# tweeq-extMod_DualSidePB.net
KiCad netlist of a schematic drawn in EAGLE
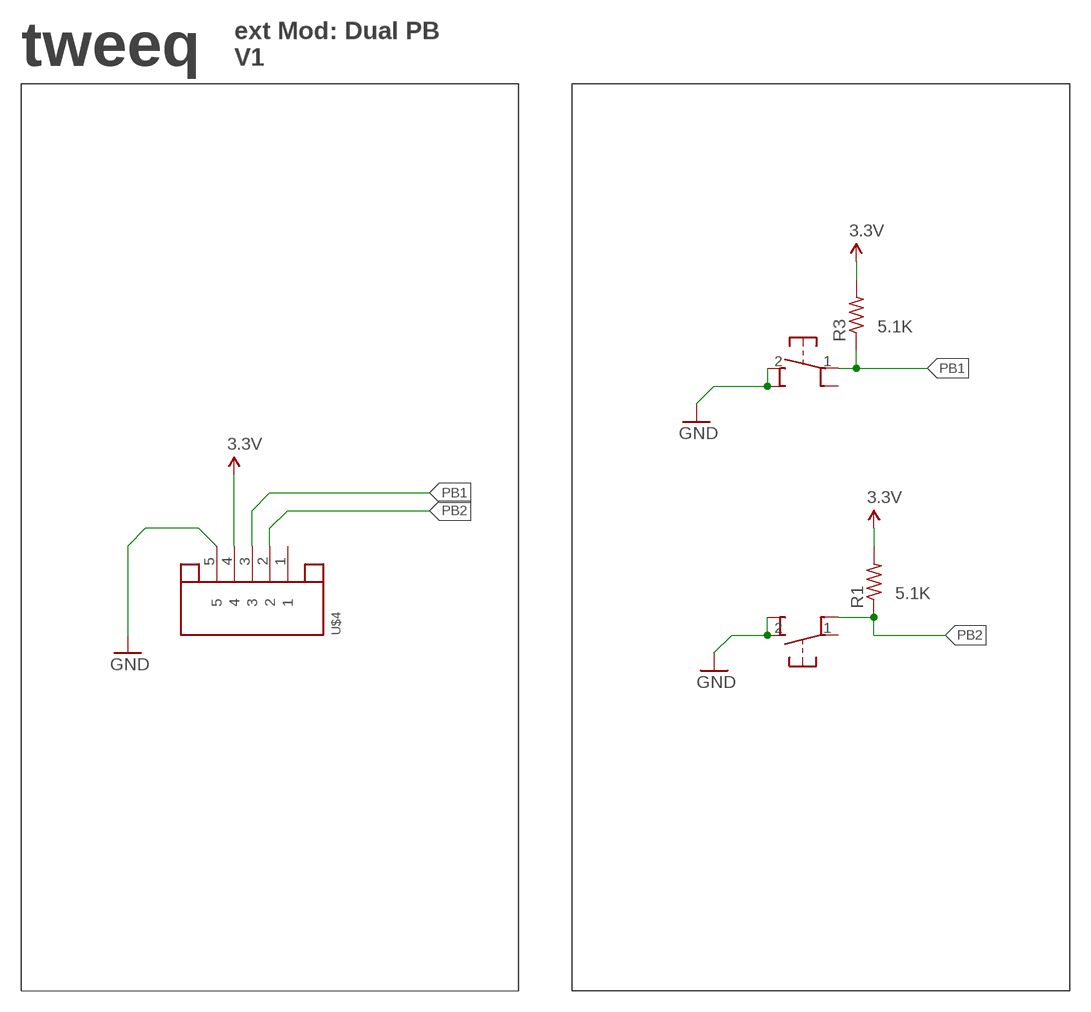
[diagram p0: schematic, sheet 1]

(export (version "E")
  (design (tool "Eeschema 10.0.6"))
  (components
    (comp (ref "R1")
      (value "5.1K")
      (footprint "eagle-import:R0402")
      (libsource (lib "eagle-import") (part "R-US_R0402"))
    )
    (comp (ref "R3")
      (value "5.1K")
      (footprint "eagle-import:R0402")
      (libsource (lib "eagle-import") (part "R-US_R0402"))
    )
    (comp (ref "U$2")
      (value "PB_MICRO_SMTRIGHTANGLE")
      (footprint "eagle-import:PB_SMT_90D6.2X4.6")
      (libsource (lib "eagle-import") (part "PB_MICRO_SMTRIGHTANGLE"))
    )
    (comp (ref "U$4")
      (value "JST-5PINSH")
      (footprint "eagle-import:SH1.0-5PIN")
      (libsource (lib "eagle-import") (part "JST-5PINSH"))
    )
    (comp (ref "U$5")
      (value "PB_MICRO_SMTRIGHTANGLE")
      (footprint "eagle-import:PB_SMT_90D6.2X4.6")
      (libsource (lib "eagle-import") (part "PB_MICRO_SMTRIGHTANGLE"))
    )
  )
  (nets
    (net (code "1") (name "3.3V") (class "Default")
      (node (ref "R1") (pin "2") (pinfunction "2_2") (pintype "passive"))
      (node (ref "R3") (pin "2") (pinfunction "2_2") (pintype "passive"))
      (node (ref "U$4") (pin "4") (pinfunction "4_4") (pintype "bidirectional"))
    )
    (net (code "2") (name "GND") (class "Default")
      (node (ref "U$2") (pin "2") (pinfunction "2_2") (pintype "passive"))
      (node (ref "U$2") (pin "2A") (pinfunction "2A_2A") (pintype "passive"))
      (node (ref "U$4") (pin "5") (pinfunction "5_5") (pintype "bidirectional"))
      (node (ref "U$5") (pin "2") (pinfunction "2_2") (pintype "passive"))
      (node (ref "U$5") (pin "2A") (pinfunction "2A_2A") (pintype "passive"))
    )
    (net (code "3") (name "PB1") (class "Default")
      (node (ref "R3") (pin "1") (pinfunction "1_1") (pintype "passive"))
      (node (ref "U$4") (pin "3") (pinfunction "3_3") (pintype "bidirectional"))
      (node (ref "U$5") (pin "1") (pinfunction "1_1") (pintype "passive"))
    )
    (net (code "4") (name "PB2") (class "Default")
      (node (ref "R1") (pin "1") (pinfunction "1_1") (pintype "passive"))
      (node (ref "U$2") (pin "1A") (pinfunction "1A_1A") (pintype "passive"))
      (node (ref "U$4") (pin "2") (pinfunction "2_2") (pintype "bidirectional"))
    )
    (net (code "5") (name "unconnected-(U$2-Pad1)") (class "Default")
      (node (ref "U$2") (pin "1") (pinfunction "1_1") (pintype "passive"))
    )
    (net (code "6") (name "unconnected-(U$4-Pad1)") (class "Default")
      (node (ref "U$4") (pin "1") (pinfunction "1_1") (pintype "bidirectional"))
    )
    (net (code "7") (name "unconnected-(U$5-Pad1A)") (class "Default")
      (node (ref "U$5") (pin "1A") (pinfunction "1A_1A") (pintype "passive"))
    )
  )
)
